# Lipmouse_Teensy.net
KiCad netlist of a schematic drawn in EAGLE
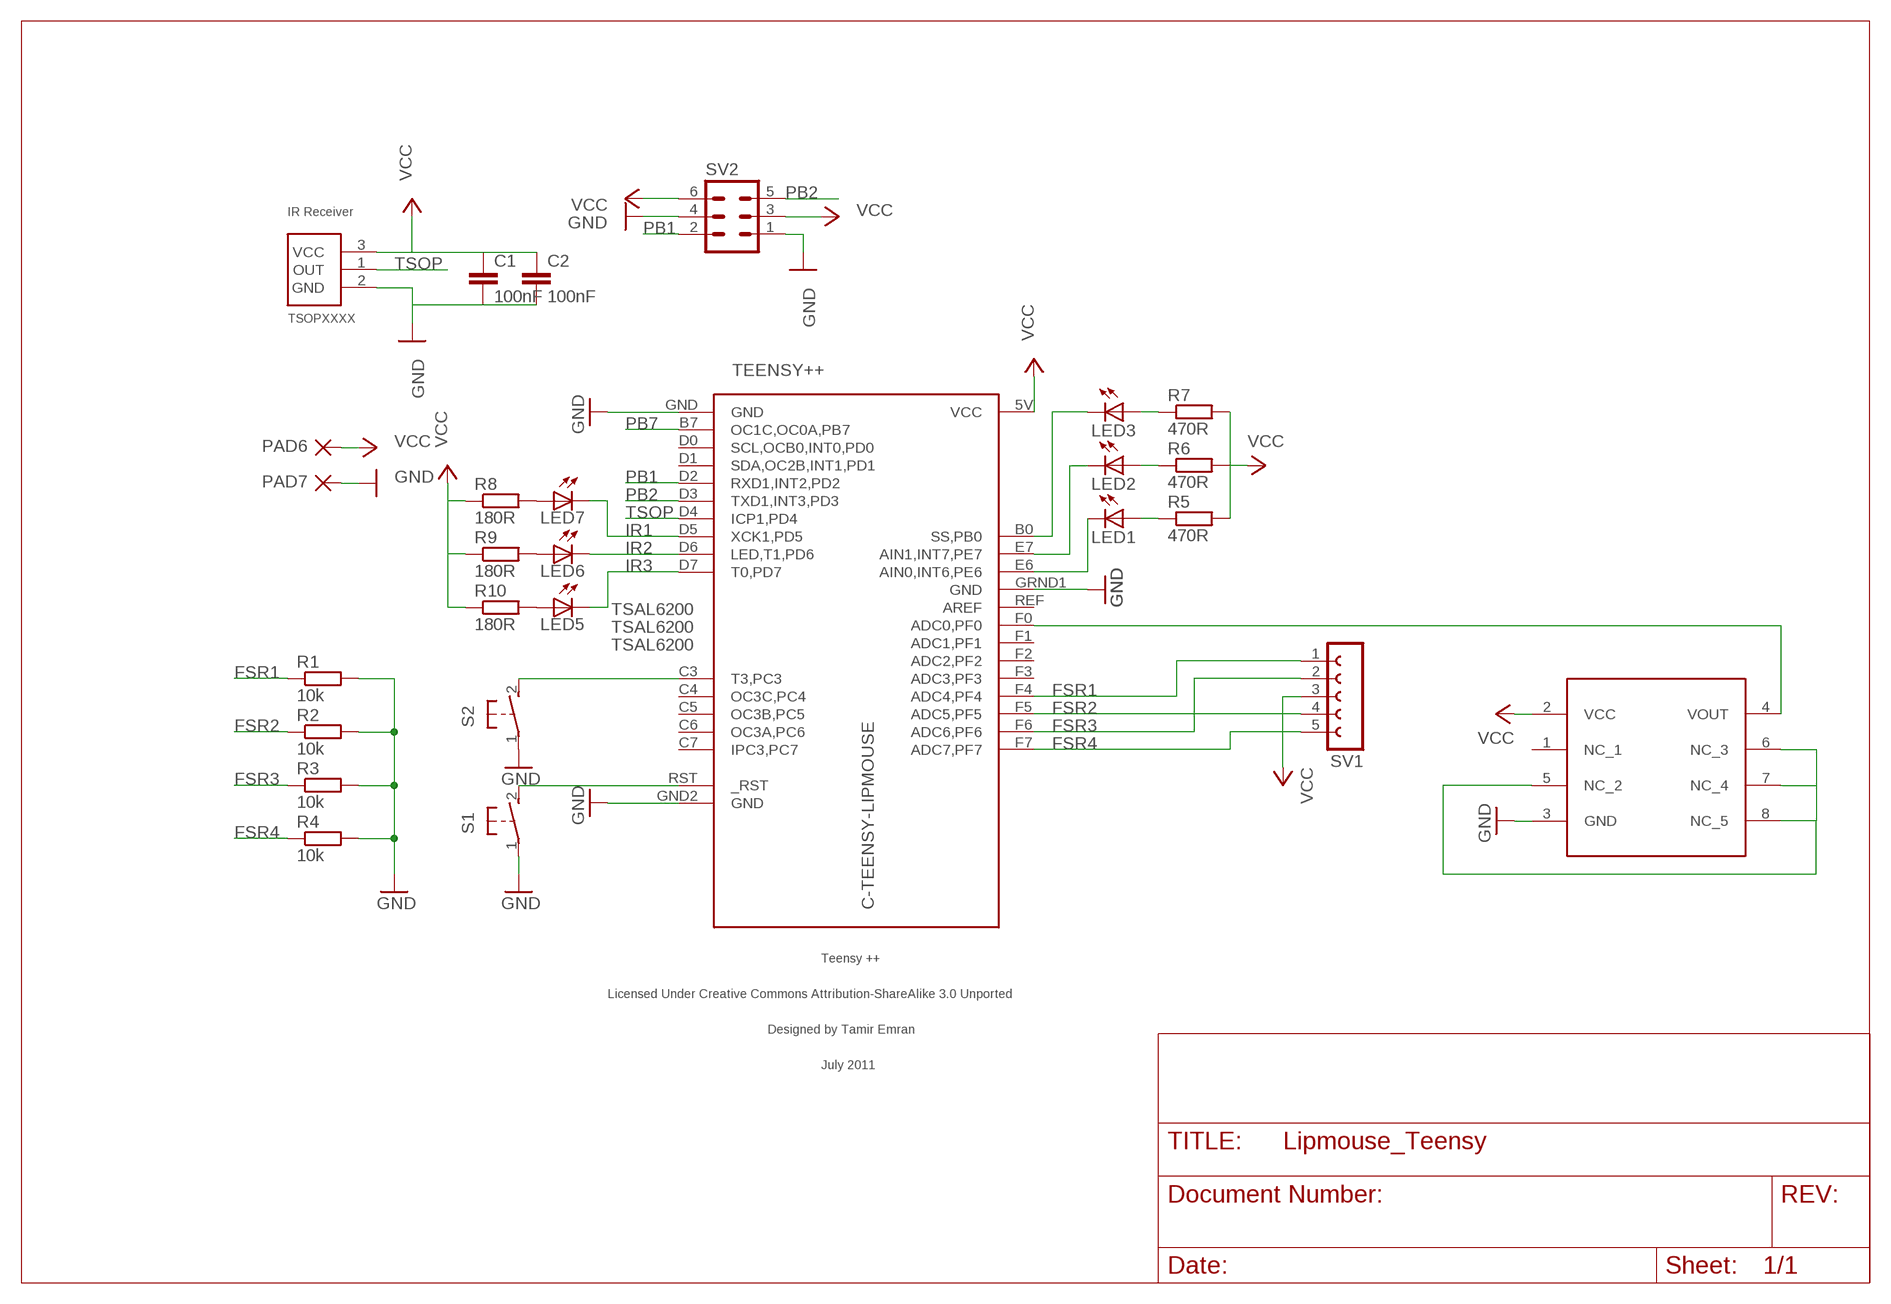
[diagram p0: schematic, sheet 1]

(export (version "E")
  (design (tool "Eeschema 10.0.6"))
  (components
    (comp (ref "C1")
      (value "100nF")
      (footprint "eagle-import:C0805K")
      (libsource (lib "eagle-import") (part "C-EUC0805K"))
    )
    (comp (ref "C2")
      (value "100nF")
      (footprint "eagle-import:C0805K")
      (libsource (lib "eagle-import") (part "C-EUC0805K"))
    )
    (comp (ref "LED1")
      (value "LED3MM")
      (footprint "eagle-import:LED3MM")
      (libsource (lib "eagle-import") (part "LED3MM"))
    )
    (comp (ref "LED2")
      (value "LED3MM")
      (footprint "eagle-import:LED3MM")
      (libsource (lib "eagle-import") (part "LED3MM"))
    )
    (comp (ref "LED3")
      (value "LED3MM")
      (footprint "eagle-import:LED3MM")
      (libsource (lib "eagle-import") (part "LED3MM"))
    )
    (comp (ref "LED5")
      (value "TSAL6200")
      (footprint "eagle-import:LED5MM")
      (libsource (lib "eagle-import") (part "led_LED5MM"))
    )
    (comp (ref "LED6")
      (value "TSAL6200")
      (footprint "eagle-import:LED5MM")
      (libsource (lib "eagle-import") (part "led_LED5MM"))
    )
    (comp (ref "LED7")
      (value "TSAL6200")
      (footprint "eagle-import:LED5MM")
      (libsource (lib "eagle-import") (part "led_LED5MM"))
    )
    (comp (ref "PAD6")
      (value "1,6/0,9")
      (footprint "eagle-import:1,6_0,9")
      (libsource (lib "eagle-import") (part "1,6/0,9"))
    )
    (comp (ref "PAD7")
      (value "1,6/0,9")
      (footprint "eagle-import:1,6_0,9")
      (libsource (lib "eagle-import") (part "1,6/0,9"))
    )
    (comp (ref "R1")
      (value "10k")
      (footprint "eagle-import:R0805W")
      (libsource (lib "eagle-import") (part "R-EU_R0805W"))
    )
    (comp (ref "R2")
      (value "10k")
      (footprint "eagle-import:R0805W")
      (libsource (lib "eagle-import") (part "R-EU_R0805W"))
    )
    (comp (ref "R3")
      (value "10k")
      (footprint "eagle-import:R0805W")
      (libsource (lib "eagle-import") (part "R-EU_R0805W"))
    )
    (comp (ref "R4")
      (value "10k")
      (footprint "eagle-import:R0805W")
      (libsource (lib "eagle-import") (part "R-EU_R0805W"))
    )
    (comp (ref "R5")
      (value "470R")
      (footprint "eagle-import:R0805W")
      (libsource (lib "eagle-import") (part "R-EU_R0805W"))
    )
    (comp (ref "R6")
      (value "470R")
      (footprint "eagle-import:R0805W")
      (libsource (lib "eagle-import") (part "R-EU_R0805W"))
    )
    (comp (ref "R7")
      (value "470R")
      (footprint "eagle-import:R0805W")
      (libsource (lib "eagle-import") (part "R-EU_R0805W"))
    )
    (comp (ref "R8")
      (value "180R")
      (footprint "eagle-import:R0805W")
      (libsource (lib "eagle-import") (part "R-EU_R0805W"))
    )
    (comp (ref "R9")
      (value "180R")
      (footprint "eagle-import:R0805W")
      (libsource (lib "eagle-import") (part "R-EU_R0805W"))
    )
    (comp (ref "R10")
      (value "180R")
      (footprint "eagle-import:R0805W")
      (libsource (lib "eagle-import") (part "R-EU_R0805W"))
    )
    (comp (ref "S1")
      (value "31-XX")
      (footprint "eagle-import:B3F-31XX")
      (libsource (lib "eagle-import") (part "31-XX"))
    )
    (comp (ref "S2")
      (value "31-XX")
      (footprint "eagle-import:B3F-31XX")
      (libsource (lib "eagle-import") (part "31-XX"))
    )
    (comp (ref "SV1")
      (value "FE05-1")
      (footprint "eagle-import:FE05-1")
      (libsource (lib "eagle-import") (part "FE05-1"))
    )
    (comp (ref "SV2")
      (value "ML6")
      (footprint "eagle-import:ML6")
      (libsource (lib "eagle-import") (part "ML6"))
    )
    (comp (ref "TEENSY++")
      (value "C-TEENSY-LIPMOUSE")
      (footprint "eagle-import:TEENSY++")
      (libsource (lib "eagle-import") (part "C-TEENSY-LIPMOUSE"))
    )
    (comp (ref "U$2")
      (value "MP3V7007GP")
      (footprint "eagle-import:SMP_MP3V7007")
      (libsource (lib "eagle-import") (part "MP3V7007GP"))
    )
    (comp (ref "U$3")
      (value "TSOP4838")
      (footprint "eagle-import:TSOP2XXX")
      (libsource (lib "eagle-import") (part "TSOP48XX"))
    )
  )
  (nets
    (net (code "1") (name "/FSR1") (class "Default")
      (node (ref "R1") (pin "1") (pinfunction "1_1") (pintype "passive"))
      (node (ref "SV1") (pin "1") (pinfunction "1_1") (pintype "passive"))
      (node (ref "TEENSY++") (pin "F4") (pinfunction "ADC4,PF4_F4") (pintype "bidirectional"))
    )
    (net (code "2") (name "/FSR2") (class "Default")
      (node (ref "R2") (pin "1") (pinfunction "1_1") (pintype "passive"))
      (node (ref "SV1") (pin "4") (pinfunction "4_4") (pintype "passive"))
      (node (ref "TEENSY++") (pin "F5") (pinfunction "ADC5,PF5_F5") (pintype "bidirectional"))
    )
    (net (code "3") (name "/FSR3") (class "Default")
      (node (ref "R3") (pin "1") (pinfunction "1_1") (pintype "passive"))
      (node (ref "SV1") (pin "2") (pinfunction "2_2") (pintype "passive"))
      (node (ref "TEENSY++") (pin "F6") (pinfunction "ADC6,PF6_F6") (pintype "bidirectional"))
    )
    (net (code "4") (name "/FSR4") (class "Default")
      (node (ref "R4") (pin "1") (pinfunction "1_1") (pintype "passive"))
      (node (ref "SV1") (pin "5") (pinfunction "5_5") (pintype "passive"))
      (node (ref "TEENSY++") (pin "F7") (pinfunction "ADC7,PF7_F7") (pintype "bidirectional"))
    )
    (net (code "5") (name "/IR1") (class "Default")
      (node (ref "LED7") (pin "K") (pinfunction "C_K") (pintype "passive"))
      (node (ref "TEENSY++") (pin "D5") (pinfunction "XCK1,PD5_D5") (pintype "bidirectional"))
    )
    (net (code "6") (name "/IR2") (class "Default")
      (node (ref "LED6") (pin "K") (pinfunction "C_K") (pintype "passive"))
      (node (ref "TEENSY++") (pin "D6") (pinfunction "LED,T1,PD6_D6") (pintype "bidirectional"))
    )
    (net (code "7") (name "/IR3") (class "Default")
      (node (ref "LED5") (pin "K") (pinfunction "C_K") (pintype "passive"))
      (node (ref "TEENSY++") (pin "D7") (pinfunction "T0,PD7_D7") (pintype "bidirectional"))
    )
    (net (code "8") (name "/PB1") (class "Default")
      (node (ref "SV2") (pin "2") (pinfunction "2_2") (pintype "passive"))
      (node (ref "TEENSY++") (pin "D2") (pinfunction "RXD1,INT2,PD2_D2") (pintype "bidirectional"))
    )
    (net (code "9") (name "/PB2") (class "Default")
      (node (ref "SV2") (pin "5") (pinfunction "5_5") (pintype "passive"))
      (node (ref "TEENSY++") (pin "D3") (pinfunction "TXD1,INT3,PD3_D3") (pintype "bidirectional"))
    )
    (net (code "10") (name "/PB7") (class "Default")
      (node (ref "TEENSY++") (pin "B7") (pinfunction "OC1C,OC0A,PB7_B7") (pintype "bidirectional"))
    )
    (net (code "11") (name "/TSOP") (class "Default")
      (node (ref "TEENSY++") (pin "D4") (pinfunction "ICP1,PD4_D4") (pintype "bidirectional"))
      (node (ref "U$3") (pin "1") (pinfunction "OUT_1") (pintype "bidirectional"))
    )
    (net (code "12") (name "GND") (class "Default")
      (node (ref "C1") (pin "2") (pinfunction "2_2") (pintype "passive"))
      (node (ref "C2") (pin "2") (pinfunction "2_2") (pintype "passive"))
      (node (ref "PAD7") (pin "1") (pinfunction "P_1") (pintype "passive"))
      (node (ref "R1") (pin "2") (pinfunction "2_2") (pintype "passive"))
      (node (ref "R2") (pin "2") (pinfunction "2_2") (pintype "passive"))
      (node (ref "R3") (pin "2") (pinfunction "2_2") (pintype "passive"))
      (node (ref "R4") (pin "2") (pinfunction "2_2") (pintype "passive"))
      (node (ref "S1") (pin "1") (pinfunction "P_1") (pintype "passive"))
      (node (ref "S2") (pin "1") (pinfunction "P_1") (pintype "passive"))
      (node (ref "SV2") (pin "1") (pinfunction "1_1") (pintype "passive"))
      (node (ref "SV2") (pin "4") (pinfunction "4_4") (pintype "passive"))
      (node (ref "TEENSY++") (pin "GND") (pinfunction "GND_GND") (pintype "power_in"))
      (node (ref "TEENSY++") (pin "GND2") (pinfunction "GND_GND2") (pintype "power_in"))
      (node (ref "TEENSY++") (pin "GRND1") (pinfunction "GND_GRND1") (pintype "power_in"))
      (node (ref "U$2") (pin "3") (pinfunction "GND_3") (pintype "bidirectional"))
      (node (ref "U$3") (pin "2") (pinfunction "GND_2") (pintype "bidirectional"))
    )
    (net (code "13") (name "Net-(LED1-C)") (class "Default")
      (node (ref "LED1") (pin "K") (pinfunction "C_K") (pintype "passive"))
      (node (ref "TEENSY++") (pin "E6") (pinfunction "AIN0,INT6,PE6_E6") (pintype "bidirectional"))
    )
    (net (code "14") (name "Net-(LED1-PadA)") (class "Default")
      (node (ref "LED1") (pin "A") (pinfunction "A_A") (pintype "passive"))
      (node (ref "R5") (pin "1") (pinfunction "1_1") (pintype "passive"))
    )
    (net (code "15") (name "Net-(LED2-C)") (class "Default")
      (node (ref "LED2") (pin "K") (pinfunction "C_K") (pintype "passive"))
      (node (ref "TEENSY++") (pin "E7") (pinfunction "AIN1,INT7,PE7_E7") (pintype "bidirectional"))
    )
    (net (code "16") (name "Net-(LED2-PadA)") (class "Default")
      (node (ref "LED2") (pin "A") (pinfunction "A_A") (pintype "passive"))
      (node (ref "R6") (pin "1") (pinfunction "1_1") (pintype "passive"))
    )
    (net (code "17") (name "Net-(LED3-C)") (class "Default")
      (node (ref "LED3") (pin "K") (pinfunction "C_K") (pintype "passive"))
      (node (ref "TEENSY++") (pin "B0") (pinfunction "SS,PB0_B0") (pintype "bidirectional"))
    )
    (net (code "18") (name "Net-(LED3-PadA)") (class "Default")
      (node (ref "LED3") (pin "A") (pinfunction "A_A") (pintype "passive"))
      (node (ref "R7") (pin "1") (pinfunction "1_1") (pintype "passive"))
    )
    (net (code "19") (name "Net-(LED5-PadA)") (class "Default")
      (node (ref "LED5") (pin "A") (pinfunction "A_A") (pintype "passive"))
      (node (ref "R10") (pin "2") (pinfunction "2_2") (pintype "passive"))
    )
    (net (code "20") (name "Net-(LED6-PadA)") (class "Default")
      (node (ref "LED6") (pin "A") (pinfunction "A_A") (pintype "passive"))
      (node (ref "R9") (pin "2") (pinfunction "2_2") (pintype "passive"))
    )
    (net (code "21") (name "Net-(LED7-PadA)") (class "Default")
      (node (ref "LED7") (pin "A") (pinfunction "A_A") (pintype "passive"))
      (node (ref "R8") (pin "2") (pinfunction "2_2") (pintype "passive"))
    )
    (net (code "22") (name "Net-(S1-S)") (class "Default")
      (node (ref "S1") (pin "2") (pinfunction "S_2") (pintype "passive"))
      (node (ref "TEENSY++") (pin "RST") (pinfunction "_RST_RST") (pintype "input"))
    )
    (net (code "23") (name "Net-(S2-S)") (class "Default")
      (node (ref "S2") (pin "2") (pinfunction "S_2") (pintype "passive"))
      (node (ref "TEENSY++") (pin "C3") (pinfunction "T3,PC3_C3") (pintype "bidirectional"))
    )
    (net (code "24") (name "Net-(TEENSY++-ADC0,PF0)") (class "Default")
      (node (ref "TEENSY++") (pin "F0") (pinfunction "ADC0,PF0_F0") (pintype "bidirectional"))
      (node (ref "U$2") (pin "4") (pinfunction "VOUT_4") (pintype "bidirectional"))
    )
    (net (code "25") (name "Net-(U$2-NC_2)") (class "Default")
      (node (ref "U$2") (pin "5") (pinfunction "NC_2_5") (pintype "bidirectional"))
      (node (ref "U$2") (pin "6") (pinfunction "NC_3_6") (pintype "bidirectional"))
      (node (ref "U$2") (pin "7") (pinfunction "NC_4_7") (pintype "bidirectional"))
      (node (ref "U$2") (pin "8") (pinfunction "NC_5_8") (pintype "bidirectional"))
    )
    (net (code "26") (name "VCC") (class "Default")
      (node (ref "C1") (pin "1") (pinfunction "1_1") (pintype "passive"))
      (node (ref "C2") (pin "1") (pinfunction "1_1") (pintype "passive"))
      (node (ref "PAD6") (pin "1") (pinfunction "P_1") (pintype "passive"))
      (node (ref "R10") (pin "1") (pinfunction "1_1") (pintype "passive"))
      (node (ref "R5") (pin "2") (pinfunction "2_2") (pintype "passive"))
      (node (ref "R6") (pin "2") (pinfunction "2_2") (pintype "passive"))
      (node (ref "R7") (pin "2") (pinfunction "2_2") (pintype "passive"))
      (node (ref "R8") (pin "1") (pinfunction "1_1") (pintype "passive"))
      (node (ref "R9") (pin "1") (pinfunction "1_1") (pintype "passive"))
      (node (ref "SV1") (pin "3") (pinfunction "3_3") (pintype "passive"))
      (node (ref "SV2") (pin "3") (pinfunction "3_3") (pintype "passive"))
      (node (ref "SV2") (pin "6") (pinfunction "6_6") (pintype "passive"))
      (node (ref "TEENSY++") (pin "5V") (pinfunction "VCC_5V") (pintype "power_in"))
      (node (ref "U$2") (pin "2") (pinfunction "VCC_2") (pintype "bidirectional"))
      (node (ref "U$3") (pin "3") (pinfunction "VCC_3") (pintype "bidirectional"))
    )
    (net (code "27") (name "unconnected-(TEENSY++-ADC1,PF1-PadF1)") (class "Default")
      (node (ref "TEENSY++") (pin "F1") (pinfunction "ADC1,PF1_F1") (pintype "bidirectional"))
    )
    (net (code "28") (name "unconnected-(TEENSY++-ADC2,PF2-PadF2)") (class "Default")
      (node (ref "TEENSY++") (pin "F2") (pinfunction "ADC2,PF2_F2") (pintype "bidirectional"))
    )
    (net (code "29") (name "unconnected-(TEENSY++-ADC3,PF3-PadF3)") (class "Default")
      (node (ref "TEENSY++") (pin "F3") (pinfunction "ADC3,PF3_F3") (pintype "bidirectional"))
    )
    (net (code "30") (name "unconnected-(TEENSY++-AREF-PadREF)") (class "Default")
      (node (ref "TEENSY++") (pin "REF") (pinfunction "AREF_REF") (pintype "input"))
    )
    (net (code "31") (name "unconnected-(TEENSY++-IPC3,PC7-PadC7)") (class "Default")
      (node (ref "TEENSY++") (pin "C7") (pinfunction "IPC3,PC7_C7") (pintype "bidirectional"))
    )
    (net (code "32") (name "unconnected-(TEENSY++-OC3A,PC6-PadC6)") (class "Default")
      (node (ref "TEENSY++") (pin "C6") (pinfunction "OC3A,PC6_C6") (pintype "bidirectional"))
    )
    (net (code "33") (name "unconnected-(TEENSY++-OC3B,PC5-PadC5)") (class "Default")
      (node (ref "TEENSY++") (pin "C5") (pinfunction "OC3B,PC5_C5") (pintype "bidirectional"))
    )
    (net (code "34") (name "unconnected-(TEENSY++-OC3C,PC4-PadC4)") (class "Default")
      (node (ref "TEENSY++") (pin "C4") (pinfunction "OC3C,PC4_C4") (pintype "bidirectional"))
    )
    (net (code "35") (name "unconnected-(TEENSY++-SCL,OCB0,INT0,PD0-PadD0)") (class "Default")
      (node (ref "TEENSY++") (pin "D0") (pinfunction "SCL,OCB0,INT0,PD0_D0") (pintype "bidirectional"))
    )
    (net (code "36") (name "unconnected-(TEENSY++-SDA,OC2B,INT1,PD1-PadD1)") (class "Default")
      (node (ref "TEENSY++") (pin "D1") (pinfunction "SDA,OC2B,INT1,PD1_D1") (pintype "bidirectional"))
    )
    (net (code "37") (name "unconnected-(U$2-NC_1-Pad1)") (class "Default")
      (node (ref "U$2") (pin "1") (pinfunction "NC_1_1") (pintype "bidirectional"))
    )
  )
)
